# ZigBee_CC2420RTC.net
KiCad netlist of a schematic drawn in Altium Designer
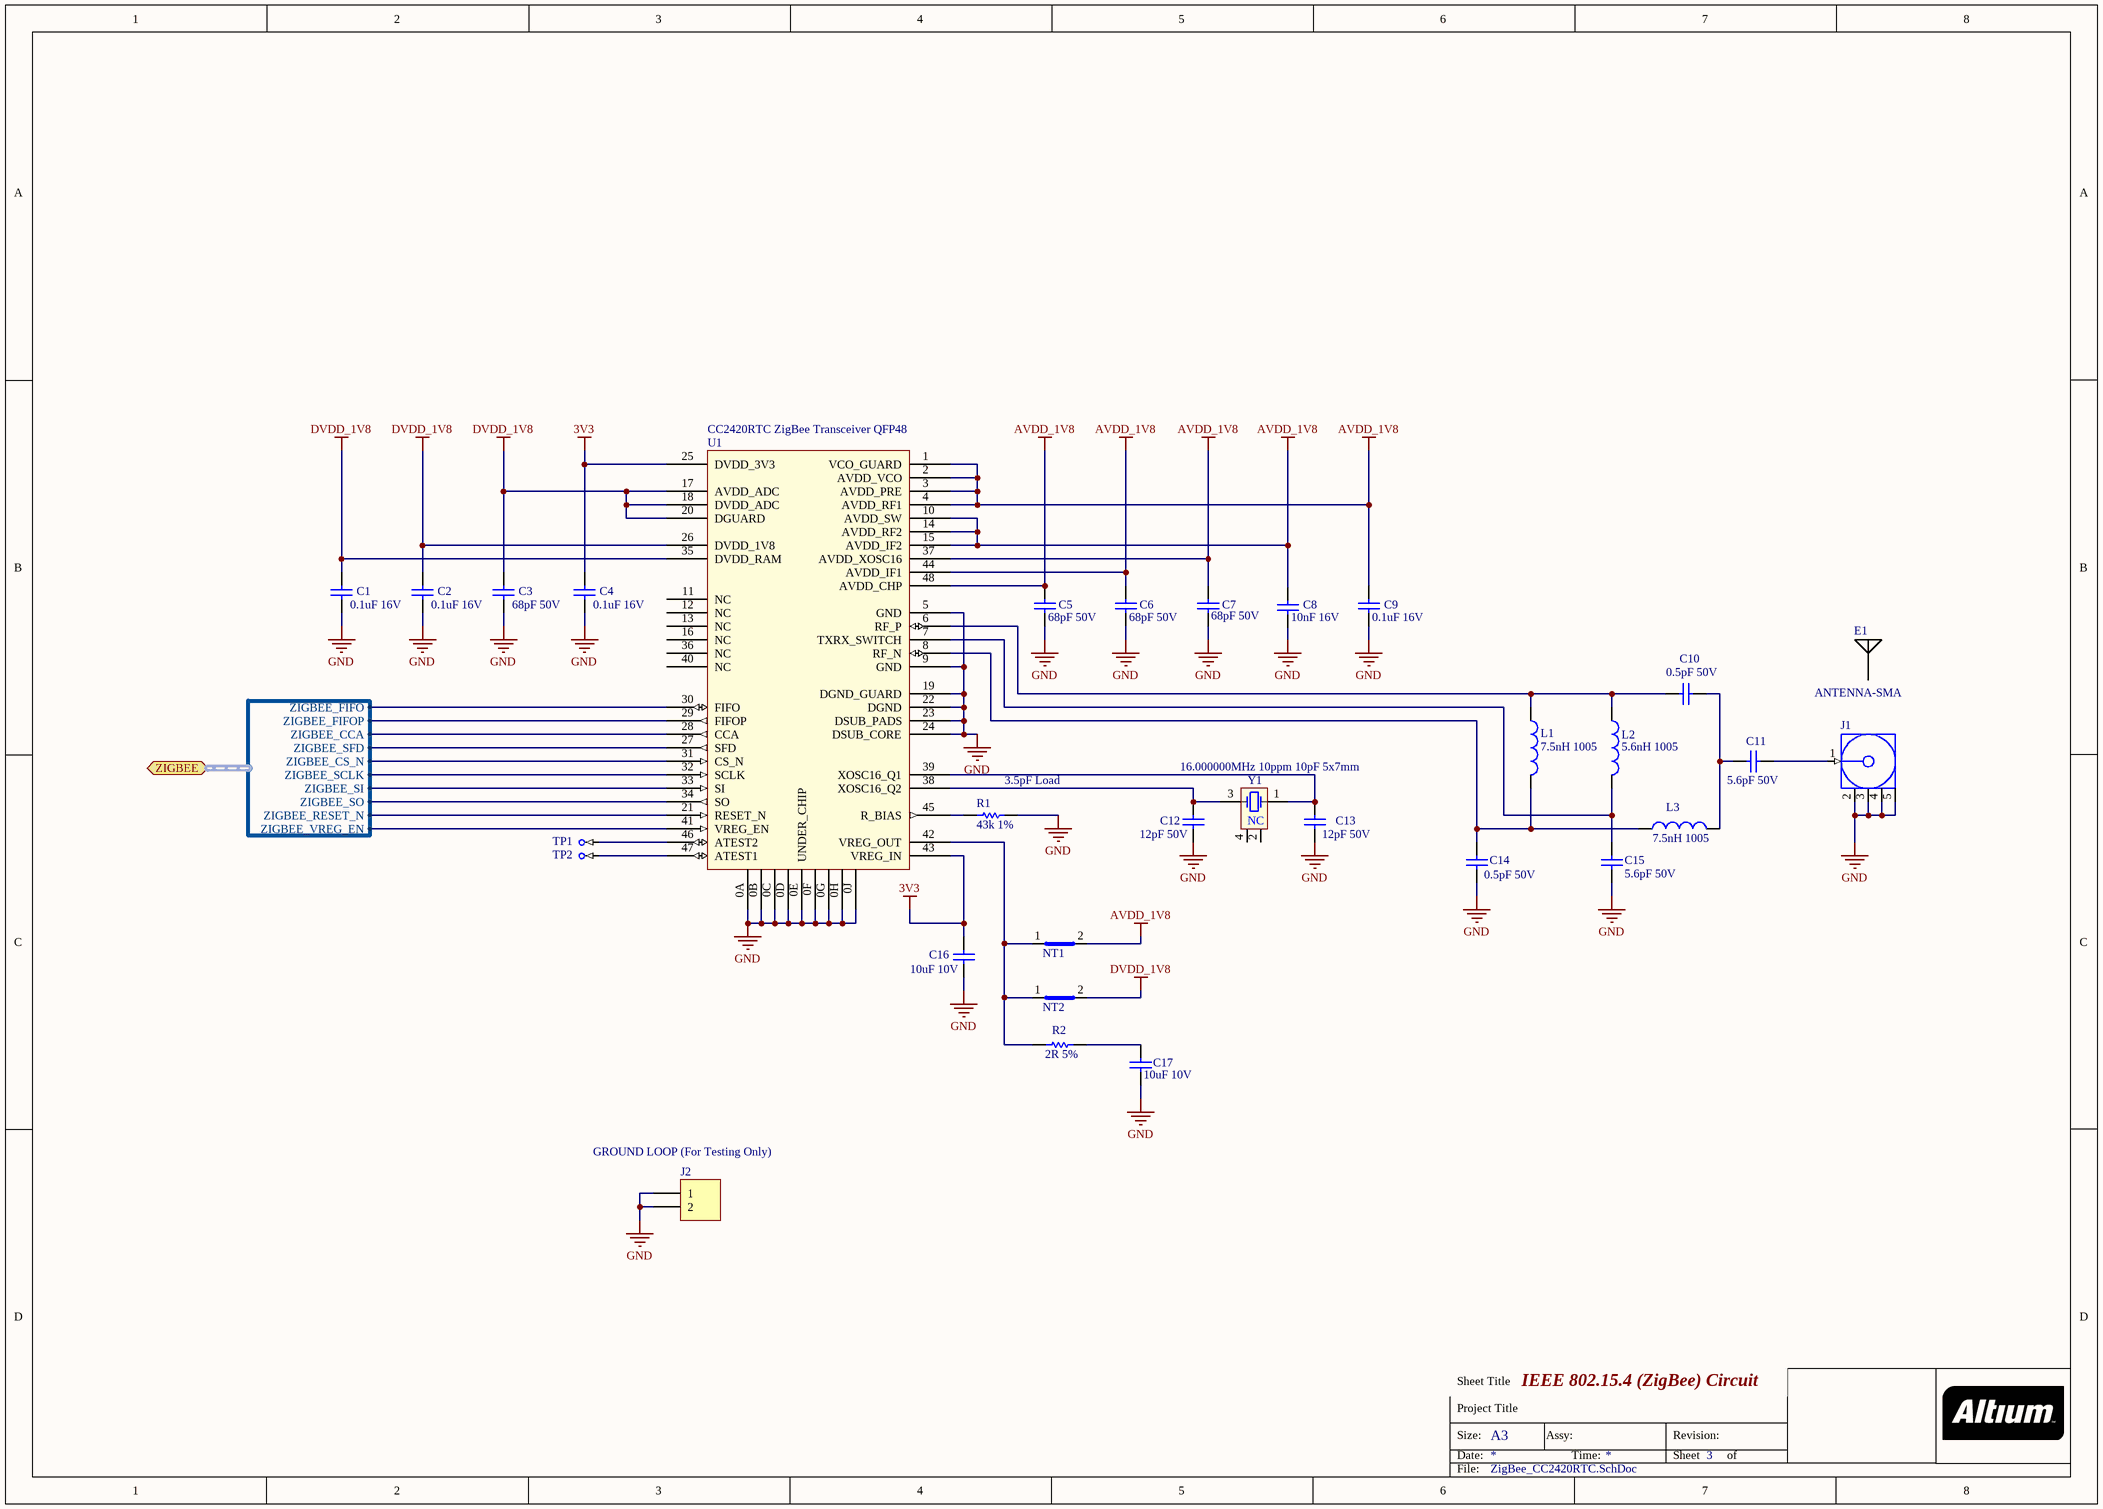
[diagram p0: ZigBee_CC2420RTC.SchDoc]

(export (version "E")
  (design (tool "Eeschema 10.0.6"))
  (components
    (comp (ref "C1")
      (value "0.1uF 16V")
      (footprint "CAPC1005-STAR")
      (description "Capacitor, Ceramic, 0.1uF 10% 16V 0402 (1005) X7R")
      (fields (field (name "TOLERANCE") "10 %"))
      (libsource (lib "AltiumDesignLibrary") (part "CAP-NP"))
    )
    (comp (ref "C2")
      (value "0.1uF 16V")
      (footprint "CAPC1005-STAR")
      (description "Capacitor, Ceramic, 0.1uF 10% 16V 0402 (1005) X7R")
      (fields (field (name "TOLERANCE") "10 %"))
      (libsource (lib "AltiumDesignLibrary") (part "CAP-NP"))
    )
    (comp (ref "C3")
      (value "68pF 50V")
      (footprint "CAPC1005-STAR")
      (description "Capacitor, Ceramic, 68pF 5% 50V 0402 (1005) COG")
      (fields (field (name "TOLERANCE") "5 %"))
      (libsource (lib "AltiumDesignLibrary") (part "CAP-NP"))
    )
    (comp (ref "C4")
      (value "0.1uF 16V")
      (footprint "CAPC1005-STAR")
      (description "Capacitor, Ceramic, 0.1uF 10% 16V 0402 (1005) X7R")
      (fields (field (name "TOLERANCE") "10 %"))
      (libsource (lib "AltiumDesignLibrary") (part "CAP-NP"))
    )
    (comp (ref "C5")
      (value "68pF 50V")
      (footprint "CAPC1005-STAR")
      (description "Capacitor, Ceramic, 68pF 5% 50V 0402 (1005) COG")
      (fields (field (name "TOLERANCE") "5 %"))
      (libsource (lib "AltiumDesignLibrary") (part "CAP-NP"))
    )
    (comp (ref "C6")
      (value "68pF 50V")
      (footprint "CAPC1005-STAR")
      (description "Capacitor, Ceramic, 68pF 5% 50V 0402 (1005) COG")
      (fields (field (name "TOLERANCE") "5 %"))
      (libsource (lib "AltiumDesignLibrary") (part "CAP-NP"))
    )
    (comp (ref "C7")
      (value "68pF 50V")
      (footprint "CAPC1005-STAR")
      (description "Capacitor, Ceramic, 68pF 5% 50V 0402 (1005) COG")
      (fields (field (name "TOLERANCE") "5 %"))
      (libsource (lib "AltiumDesignLibrary") (part "CAP-NP"))
    )
    (comp (ref "C8")
      (value "10nF 16V")
      (footprint "CAPC1005-STAR")
      (description "Capacitor, Ceramic, 10nF 10% 16V 0402 (1005) X7R")
      (fields (field (name "TOLERANCE") "10 %"))
      (libsource (lib "AltiumDesignLibrary") (part "CAP-NP"))
    )
    (comp (ref "C9")
      (value "0.1uF 16V")
      (footprint "CAPC1005-STAR")
      (description "Capacitor, Ceramic, 0.1uF 10% 16V 0402 (1005) X7R")
      (fields (field (name "TOLERANCE") "10 %"))
      (libsource (lib "AltiumDesignLibrary") (part "CAP-NP"))
    )
    (comp (ref "C10")
      (value "0.5pF 50V")
      (footprint "CAPC1005-STAR")
      (description "Capacitor, Ceramic, 0.5pF 50V 0402 (1005) COG")
      (fields (field (name "TOLERANCE") "20 %"))
      (libsource (lib "AltiumDesignLibrary") (part "CAP-NP"))
    )
    (comp (ref "C11")
      (value "5.6pF 50V")
      (footprint "CAPC1005-STAR")
      (description "Capacitor, Ceramic, 5.6pF 5% 50V 0402 (1005) COG")
      (fields (field (name "TOLERANCE") "5 %"))
      (libsource (lib "AltiumDesignLibrary") (part "CAP-NP"))
    )
    (comp (ref "C12")
      (value "12pF 50V")
      (footprint "CAPC1005-STAR")
      (description "Capacitor, Ceramic, 12pF 2% 50V 0402 (1005) COG")
      (fields (field (name "TOLERANCE") "2 %"))
      (libsource (lib "AltiumDesignLibrary") (part "CAP-NP"))
    )
    (comp (ref "C13")
      (value "12pF 50V")
      (footprint "CAPC1005-STAR")
      (description "Capacitor, Ceramic, 12pF 2% 50V 0402 (1005) COG")
      (fields (field (name "TOLERANCE") "2 %"))
      (libsource (lib "AltiumDesignLibrary") (part "CAP-NP"))
    )
    (comp (ref "C14")
      (value "0.5pF 50V")
      (footprint "CAPC1005-STAR")
      (description "Capacitor, Ceramic, 0.5pF 50V 0402 (1005) COG")
      (fields (field (name "TOLERANCE") "20 %"))
      (libsource (lib "AltiumDesignLibrary") (part "CAP-NP"))
    )
    (comp (ref "C15")
      (value "5.6pF 50V")
      (footprint "CAPC1005-STAR")
      (description "Capacitor, Ceramic, 5.6pF 5% 50V 0402 (1005) COG")
      (fields (field (name "TOLERANCE") "5 %"))
      (libsource (lib "AltiumDesignLibrary") (part "CAP-NP"))
    )
    (comp (ref "C16")
      (value "10uF 10V")
      (footprint "CAPC3216-STAR")
      (description "Capacitor, Ceramic, 10uF 10% 10V 1206 (3216) X5R")
      (fields (field (name "TOLERANCE") "10 %"))
      (libsource (lib "AltiumDesignLibrary") (part "CAP-NP"))
    )
    (comp (ref "C17")
      (value "10uF 10V")
      (footprint "CAPC3216-STAR")
      (description "Capacitor, Ceramic, 10uF 10% 10V 1206 (3216) X5R")
      (fields (field (name "TOLERANCE") "10 %"))
      (libsource (lib "AltiumDesignLibrary") (part "CAP-NP"))
    )
    (comp (ref "E1")
      (value "ANTENNA-SMA")
      (description "Antenna, 2.45GHz 1/4 Wave 50R SMA Antenna")
      (libsource (lib "AltiumDesignLibrary") (part "ANTENNA-0-PIN"))
    )
    (comp (ref "J1")
      (value "SMA 5-pin Vertical Jack 50R")
      (footprint "HDR-SMA-THD-5-PIN")
      (description "SMA RF Coaxial PCB Connector, 5-pin Through-hole, Vertical Mount Socket, 50 ohm impedance")
      (libsource (lib "AltiumDesignLibrary") (part "CON-HDR-COAXIAL-5-PIN"))
    )
    (comp (ref "J2")
      (value "1x2 HEADER MALE")
      (footprint "HDR1X2")
      (description "Header IDC, 2 x 1 Pin Vertical 2.54mm Pitch (Non-Boxed, Male)")
      (libsource (lib "AltiumDesignLibrary") (part "CON-HDR-1x2-STR"))
    )
    (comp (ref "L1")
      (value "7.5nH 1005")
      (footprint "INDC1005")
      (description "Inductor, Chip 7.5nH 300mA DCR=0.24 ohm, High Frequency 0402 (1005)")
      (libsource (lib "AltiumDesignLibrary") (part "IND"))
    )
    (comp (ref "L2")
      (value "5.6nH 1005")
      (footprint "INDC1005")
      (description "Inductor, Chip 5.6nH 300mA DCR=0.2 ohm, High Frequency 0402 (1005)")
      (libsource (lib "AltiumDesignLibrary") (part "IND"))
    )
    (comp (ref "L3")
      (value "7.5nH 1005")
      (footprint "INDC1005")
      (description "Inductor, Chip 7.5nH 300mA DCR=0.24 ohm, High Frequency 0402 (1005)")
      (libsource (lib "AltiumDesignLibrary") (part "IND"))
    )
    (comp (ref "NT1")
      (value "Net Tie SMT2")
      (footprint "NETTIE-SMT2-16X11")
      (description "Net-Tie, Surface Mount, 2 x 0.8mm x 0.4mm SMT Pads - For 0.4mm Track")
      (libsource (lib "AltiumDesignLibrary") (part "NETTIE-SMT2"))
    )
    (comp (ref "NT2")
      (value "Net Tie SMT2")
      (footprint "NETTIE-SMT2-16X11")
      (description "Net-Tie, Surface Mount, 2 x 0.8mm x 0.4mm SMT Pads - For 0.4mm Track")
      (libsource (lib "AltiumDesignLibrary") (part "NETTIE-SMT2"))
    )
    (comp (ref "R1")
      (value "43k 1%")
      (footprint "RESC1005-STAR")
      (description "Resistor, 43k 1% 0402 (1005)")
      (fields (field (name "TOLERANCE") "1 %"))
      (libsource (lib "AltiumDesignLibrary") (part "RES"))
    )
    (comp (ref "R2")
      (value "2R 5%")
      (footprint "RESC1005-STAR")
      (description "Resistopr, 2R 5% 0402 (1005)")
      (fields (field (name "TOLERANCE") "5 %"))
      (libsource (lib "AltiumDesignLibrary") (part "RES"))
    )
    (comp (ref "TP1")
      (value "TestPin")
      (footprint "TestPin")
      (description "Test Point, PCB Mount with Silkscreen Box")
      (libsource (lib "AltiumDesignLibrary") (part "TestPin"))
    )
    (comp (ref "TP2")
      (value "TestPin")
      (footprint "TestPin")
      (description "Test Point, PCB Mount with Silkscreen Box")
      (libsource (lib "AltiumDesignLibrary") (part "TestPin"))
    )
    (comp (ref "U1")
      (value "CC2420RTC ZigBee Transceiver QFP48")
      (footprint "SQFP50P700X700-48")
      (description "CC2420RTC, 2.45GHz IEEE 802.15.4 (Zigbee) RF Transceiver QFP48")
      (libsource (lib "AltiumDesignLibrary") (part "IC-CC2420RTC"))
    )
    (comp (ref "Y1")
      (value "16.000000MHz 10ppm 10pF 5x7mm")
      (footprint "XTAL-7X5")
      (description "Crystal, 16.000000MHz, 5x7mm, 10ppm 10ppm 10pF")
      (libsource (lib "AltiumDesignLibrary") (part "CRYSTAL-4PINS-1-TO-3"))
    )
  )
  (nets
    (net (code "2") (name "/ZIGBEE_CCA") (class "Default")
      (node (ref "U1") (pin "28") (pinfunction "CCA_28") (pintype "output"))
    )
    (net (code "3") (name "/ZIGBEE_CS_N") (class "Default")
      (node (ref "U1") (pin "31") (pinfunction "CS_N_31") (pintype "input"))
    )
    (net (code "4") (name "/ZIGBEE_FIFO") (class "Default")
      (node (ref "U1") (pin "30") (pinfunction "FIFO_30") (pintype "bidirectional"))
    )
    (net (code "5") (name "/ZIGBEE_FIFOP") (class "Default")
      (node (ref "U1") (pin "29") (pinfunction "FIFOP_29") (pintype "output"))
    )
    (net (code "6") (name "/ZIGBEE_RESET_N") (class "Default")
      (node (ref "U1") (pin "21") (pinfunction "RESET_N_21") (pintype "input"))
    )
    (net (code "7") (name "/ZIGBEE_SCLK") (class "Default")
      (node (ref "U1") (pin "32") (pinfunction "SCLK_32") (pintype "input"))
    )
    (net (code "8") (name "/ZIGBEE_SFD") (class "Default")
      (node (ref "U1") (pin "27") (pinfunction "SFD_27") (pintype "output"))
    )
    (net (code "9") (name "/ZIGBEE_SI") (class "Default")
      (node (ref "U1") (pin "33") (pinfunction "SI_33") (pintype "input"))
    )
    (net (code "10") (name "/ZIGBEE_SO") (class "Default")
      (node (ref "U1") (pin "34") (pinfunction "SO_34") (pintype "output"))
    )
    (net (code "11") (name "/ZIGBEE_VREG_EN") (class "Default")
      (node (ref "U1") (pin "41") (pinfunction "VREG_EN_41") (pintype "input"))
    )
    (net (code "13") (name "3V3") (class "Default")
      (node (ref "C16") (pin "1") (pinfunction "1_1") (pintype "passive"))
      (node (ref "C4") (pin "1") (pinfunction "1_1") (pintype "passive"))
      (node (ref "U1") (pin "25") (pinfunction "DVDD_3V3_25") (pintype "passive"))
      (node (ref "U1") (pin "43") (pinfunction "VREG_IN_43") (pintype "passive"))
    )
    (net (code "14") (name "AVDD_1V8") (class "Default")
      (node (ref "C5") (pin "1") (pinfunction "1_1") (pintype "passive"))
      (node (ref "C6") (pin "1") (pinfunction "1_1") (pintype "passive"))
      (node (ref "C7") (pin "1") (pinfunction "1_1") (pintype "passive"))
      (node (ref "C8") (pin "1") (pinfunction "1_1") (pintype "passive"))
      (node (ref "C9") (pin "1") (pinfunction "1_1") (pintype "passive"))
      (node (ref "NT1") (pin "2") (pinfunction "Net2_2") (pintype "passive"))
      (node (ref "U1") (pin "1") (pinfunction "VCO_GUARD_1") (pintype "passive"))
      (node (ref "U1") (pin "10") (pinfunction "AVDD_SW_10") (pintype "passive"))
      (node (ref "U1") (pin "14") (pinfunction "AVDD_RF2_14") (pintype "passive"))
      (node (ref "U1") (pin "15") (pinfunction "AVDD_IF2_15") (pintype "passive"))
      (node (ref "U1") (pin "2") (pinfunction "AVDD_VCO_2") (pintype "passive"))
      (node (ref "U1") (pin "3") (pinfunction "AVDD_PRE_3") (pintype "passive"))
      (node (ref "U1") (pin "37") (pinfunction "AVDD_XOSC16_37") (pintype "passive"))
      (node (ref "U1") (pin "4") (pinfunction "AVDD_RF1_4") (pintype "passive"))
      (node (ref "U1") (pin "44") (pinfunction "AVDD_IF1_44") (pintype "passive"))
      (node (ref "U1") (pin "48") (pinfunction "AVDD_CHP_48") (pintype "passive"))
    )
    (net (code "15") (name "DVDD_1V8") (class "Default")
      (node (ref "C1") (pin "1") (pinfunction "1_1") (pintype "passive"))
      (node (ref "C2") (pin "1") (pinfunction "1_1") (pintype "passive"))
      (node (ref "C3") (pin "1") (pinfunction "1_1") (pintype "passive"))
      (node (ref "NT2") (pin "2") (pinfunction "Net2_2") (pintype "passive"))
      (node (ref "U1") (pin "17") (pinfunction "AVDD_ADC_17") (pintype "passive"))
      (node (ref "U1") (pin "18") (pinfunction "DVDD_ADC_18") (pintype "passive"))
      (node (ref "U1") (pin "20") (pinfunction "DGUARD_20") (pintype "passive"))
      (node (ref "U1") (pin "26") (pinfunction "DVDD_1V8_26") (pintype "passive"))
      (node (ref "U1") (pin "35") (pinfunction "DVDD_RAM_35") (pintype "passive"))
    )
    (net (code "16") (name "GND") (class "Default")
      (node (ref "C1") (pin "2") (pinfunction "2_2") (pintype "passive"))
      (node (ref "C12") (pin "1") (pinfunction "1_1") (pintype "passive"))
      (node (ref "C13") (pin "1") (pinfunction "1_1") (pintype "passive"))
      (node (ref "C14") (pin "1") (pinfunction "1_1") (pintype "passive"))
      (node (ref "C15") (pin "2") (pinfunction "2_2") (pintype "passive"))
      (node (ref "C16") (pin "2") (pinfunction "2_2") (pintype "passive"))
      (node (ref "C17") (pin "2") (pinfunction "2_2") (pintype "passive"))
      (node (ref "C2") (pin "2") (pinfunction "2_2") (pintype "passive"))
      (node (ref "C3") (pin "2") (pinfunction "2_2") (pintype "passive"))
      (node (ref "C4") (pin "2") (pinfunction "2_2") (pintype "passive"))
      (node (ref "C5") (pin "2") (pinfunction "2_2") (pintype "passive"))
      (node (ref "C6") (pin "2") (pinfunction "2_2") (pintype "passive"))
      (node (ref "C7") (pin "2") (pinfunction "2_2") (pintype "passive"))
      (node (ref "C8") (pin "2") (pinfunction "2_2") (pintype "passive"))
      (node (ref "C9") (pin "2") (pinfunction "2_2") (pintype "passive"))
      (node (ref "J1") (pin "2") (pinfunction "GND_2") (pintype "passive"))
      (node (ref "J1") (pin "3") (pinfunction "GND_3") (pintype "passive"))
      (node (ref "J1") (pin "4") (pinfunction "GND_4") (pintype "passive"))
      (node (ref "J1") (pin "5") (pinfunction "GND_5") (pintype "passive"))
      (node (ref "J2") (pin "1") (pinfunction "1_1") (pintype "passive"))
      (node (ref "J2") (pin "2") (pinfunction "2_2") (pintype "passive"))
      (node (ref "R1") (pin "2") (pinfunction "2_2") (pintype "passive"))
      (node (ref "U1") (pin "0A") (pintype "passive"))
      (node (ref "U1") (pin "0B") (pintype "passive"))
      (node (ref "U1") (pin "0C") (pintype "passive"))
      (node (ref "U1") (pin "0D") (pintype "passive"))
      (node (ref "U1") (pin "0E") (pinfunction "UNDER_CHIP_0E") (pintype "passive"))
      (node (ref "U1") (pin "0F") (pintype "passive"))
      (node (ref "U1") (pin "0G") (pintype "passive"))
      (node (ref "U1") (pin "0H") (pintype "passive"))
      (node (ref "U1") (pin "0J") (pintype "passive"))
      (node (ref "U1") (pin "19") (pinfunction "DGND_GUARD_19") (pintype "passive"))
      (node (ref "U1") (pin "22") (pinfunction "DGND_22") (pintype "passive"))
      (node (ref "U1") (pin "23") (pinfunction "DSUB_PADS_23") (pintype "passive"))
      (node (ref "U1") (pin "24") (pinfunction "DSUB_CORE_24") (pintype "passive"))
      (node (ref "U1") (pin "5") (pinfunction "GND_5") (pintype "passive"))
      (node (ref "U1") (pin "9") (pinfunction "GND_9") (pintype "passive"))
    )
    (net (code "17") (name "Net-(C10-Pad2)") (class "Default")
      (node (ref "C10") (pin "2") (pinfunction "2_2") (pintype "passive"))
      (node (ref "C11") (pin "1") (pinfunction "1_1") (pintype "passive"))
      (node (ref "L3") (pin "2") (pinfunction "2_2") (pintype "passive"))
    )
    (net (code "18") (name "Net-(C17-Pad1)") (class "Default")
      (node (ref "C17") (pin "1") (pinfunction "1_1") (pintype "passive"))
      (node (ref "R2") (pin "2") (pinfunction "2_2") (pintype "passive"))
    )
    (net (code "19") (name "Net-(J1-Signal)") (class "Default")
      (node (ref "C11") (pin "2") (pinfunction "2_2") (pintype "passive"))
      (node (ref "J1") (pin "1") (pinfunction "Signal_1") (pintype "input"))
    )
    (net (code "20") (name "Net-(NT1-Net1)") (class "Default")
      (node (ref "NT1") (pin "1") (pinfunction "Net1_1") (pintype "passive"))
      (node (ref "NT2") (pin "1") (pinfunction "Net1_1") (pintype "passive"))
      (node (ref "R2") (pin "1") (pinfunction "1_1") (pintype "passive"))
      (node (ref "U1") (pin "42") (pinfunction "VREG_OUT_42") (pintype "passive"))
    )
    (net (code "21") (name "Net-(U1-ATEST1)") (class "Default")
      (node (ref "TP2") (pin "1") (pinfunction "1_1") (pintype "input"))
      (node (ref "U1") (pin "47") (pinfunction "ATEST1_47") (pintype "bidirectional"))
    )
    (net (code "22") (name "Net-(U1-ATEST2)") (class "Default")
      (node (ref "TP1") (pin "1") (pinfunction "1_1") (pintype "input"))
      (node (ref "U1") (pin "46") (pinfunction "ATEST2_46") (pintype "bidirectional"))
    )
    (net (code "23") (name "Net-(U1-RF_N)") (class "Default")
      (node (ref "C14") (pin "2") (pinfunction "2_2") (pintype "passive"))
      (node (ref "L1") (pin "2") (pinfunction "2_2") (pintype "passive"))
      (node (ref "L3") (pin "1") (pinfunction "1_1") (pintype "passive"))
      (node (ref "U1") (pin "8") (pinfunction "RF_N_8") (pintype "bidirectional"))
    )
    (net (code "24") (name "Net-(U1-RF_P)") (class "Default")
      (node (ref "C10") (pin "1") (pinfunction "1_1") (pintype "passive"))
      (node (ref "L1") (pin "1") (pinfunction "1_1") (pintype "passive"))
      (node (ref "L2") (pin "1") (pinfunction "1_1") (pintype "passive"))
      (node (ref "U1") (pin "6") (pinfunction "RF_P_6") (pintype "bidirectional"))
    )
    (net (code "25") (name "Net-(U1-R_BIAS)") (class "Default")
      (node (ref "R1") (pin "1") (pinfunction "1_1") (pintype "passive"))
      (node (ref "U1") (pin "45") (pinfunction "R_BIAS_45") (pintype "output"))
    )
    (net (code "26") (name "Net-(U1-TXRX_SWITCH)") (class "Default")
      (node (ref "C15") (pin "1") (pinfunction "1_1") (pintype "passive"))
      (node (ref "L2") (pin "2") (pinfunction "2_2") (pintype "passive"))
      (node (ref "U1") (pin "7") (pinfunction "TXRX_SWITCH_7") (pintype "passive"))
    )
    (net (code "27") (name "Net-(U1-XOSC16_Q1)") (class "Default")
      (node (ref "C13") (pin "2") (pinfunction "2_2") (pintype "passive"))
      (node (ref "U1") (pin "39") (pinfunction "XOSC16_Q1_39") (pintype "passive"))
      (node (ref "Y1") (pin "1") (pinfunction "X1_1") (pintype "passive"))
    )
    (net (code "28") (name "Net-(U1-XOSC16_Q2)") (class "Default")
      (node (ref "C12") (pin "2") (pinfunction "2_2") (pintype "passive"))
      (node (ref "U1") (pin "38") (pinfunction "XOSC16_Q2_38") (pintype "passive"))
      (node (ref "Y1") (pin "3") (pinfunction "X2_3") (pintype "passive"))
    )
    (net (code "29") (name "unconnected-(U1-NC-Pad11)") (class "Default")
      (node (ref "U1") (pin "11") (pinfunction "NC_11") (pintype "passive"))
    )
    (net (code "30") (name "unconnected-(U1-NC-Pad12)") (class "Default")
      (node (ref "U1") (pin "12") (pinfunction "NC_12") (pintype "passive"))
    )
    (net (code "31") (name "unconnected-(U1-NC-Pad13)") (class "Default")
      (node (ref "U1") (pin "13") (pinfunction "NC_13") (pintype "passive"))
    )
    (net (code "32") (name "unconnected-(U1-NC-Pad16)") (class "Default")
      (node (ref "U1") (pin "16") (pinfunction "NC_16") (pintype "passive"))
    )
    (net (code "33") (name "unconnected-(U1-NC-Pad36)") (class "Default")
      (node (ref "U1") (pin "36") (pinfunction "NC_36") (pintype "passive"))
    )
    (net (code "34") (name "unconnected-(U1-NC-Pad40)") (class "Default")
      (node (ref "U1") (pin "40") (pinfunction "NC_40") (pintype "passive"))
    )
    (net (code "35") (name "unconnected-(Y1-NC-Pad2)") (class "Default")
      (node (ref "Y1") (pin "2") (pinfunction "NC_2") (pintype "passive"))
    )
    (net (code "36") (name "unconnected-(Y1-NC-Pad4)") (class "Default")
      (node (ref "Y1") (pin "4") (pinfunction "NC_4") (pintype "passive"))
    )
  )
)
